# KSM_ICSP.net
KiCad netlist of a schematic drawn in EAGLE
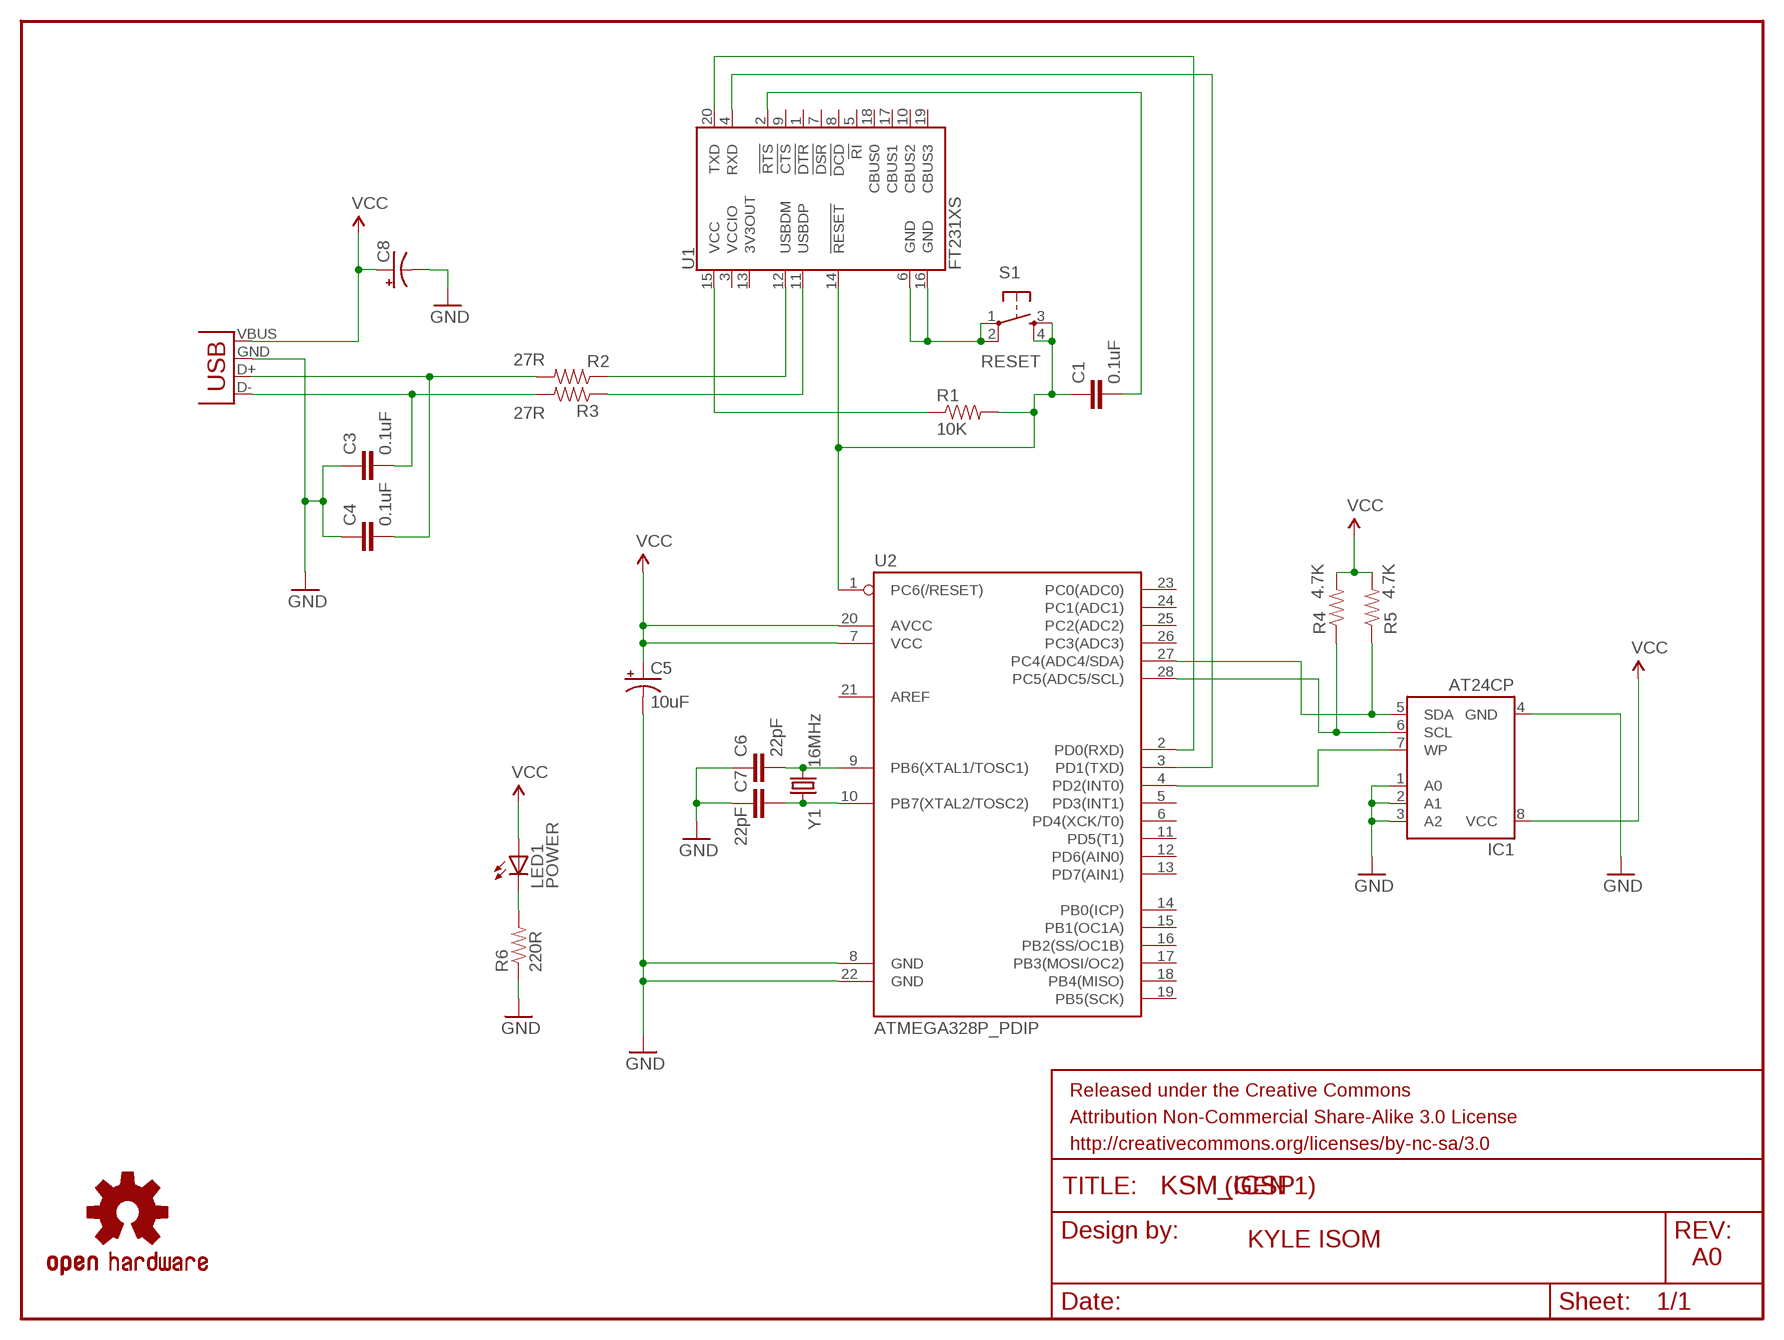
[diagram p0: schematic, sheet 1]

(export (version "E")
  (design (tool "Eeschema 10.0.6"))
  (components
    (comp (ref "C1")
      (value "0.1uF")
      (footprint "eagle-import:CAP-PTH-SMALL")
      (libsource (lib "eagle-import") (part "CAPPTH"))
    )
    (comp (ref "C3")
      (value "0.1uF")
      (footprint "eagle-import:CAP-PTH-SMALL")
      (libsource (lib "eagle-import") (part "CAPPTH"))
    )
    (comp (ref "C4")
      (value "0.1uF")
      (footprint "eagle-import:CAP-PTH-SMALL")
      (libsource (lib "eagle-import") (part "CAPPTH"))
    )
    (comp (ref "C5")
      (value "10uF")
      (footprint "eagle-import:CPOL-RADIAL-10UF-25V")
      (libsource (lib "eagle-import") (part "CAP_POLPTH2"))
    )
    (comp (ref "C6")
      (value "22pF")
      (footprint "eagle-import:CAP-PTH-SMALL")
      (libsource (lib "eagle-import") (part "CAPPTH"))
    )
    (comp (ref "C7")
      (value "22pF")
      (footprint "eagle-import:CAP-PTH-SMALL")
      (libsource (lib "eagle-import") (part "CAPPTH"))
    )
    (comp (ref "C8")
      (value "CAP_POLPTH2")
      (footprint "eagle-import:CPOL-RADIAL-10UF-25V")
      (libsource (lib "eagle-import") (part "CAP_POLPTH2"))
    )
    (comp (ref "FRAME1")
      (value "FRAME-LETTER")
      (footprint "eagle-import:CREATIVE_COMMONS")
      (libsource (lib "eagle-import") (part "FRAME-LETTER"))
    )
    (comp (ref "IC1")
      (value "AT24CP")
      (footprint "eagle-import:DIL08")
      (fields (field (name "MPN") "AT24C1024BW-SH-B"))
      (libsource (lib "eagle-import") (part "AT24CP"))
    )
    (comp (ref "JP1")
      (value "USB-A-H")
      (footprint "eagle-import:USB-A-H")
      (libsource (lib "eagle-import") (part "USB-A-H"))
    )
    (comp (ref "LED1")
      (value "POWER")
      (footprint "eagle-import:LED3MM")
      (libsource (lib "eagle-import") (part "LED3MM"))
    )
    (comp (ref "LOGO1")
      (value "OSHW-LOGOL")
      (footprint "eagle-import:OSHW-LOGO-L")
      (libsource (lib "eagle-import") (part "OSHW-LOGOL"))
    )
    (comp (ref "R1")
      (value "10K")
      (footprint "eagle-import:AXIAL-0.4")
      (libsource (lib "eagle-import") (part "RESISTORPTH-1/4W"))
    )
    (comp (ref "R2")
      (value "27R")
      (footprint "eagle-import:AXIAL-0.4")
      (libsource (lib "eagle-import") (part "RESISTORPTH-1/4W"))
    )
    (comp (ref "R3")
      (value "27R")
      (footprint "eagle-import:AXIAL-0.4")
      (libsource (lib "eagle-import") (part "RESISTORPTH-1/4W"))
    )
    (comp (ref "R4")
      (value "4.7K")
      (footprint "eagle-import:AXIAL-0.4")
      (libsource (lib "eagle-import") (part "RESISTORPTH-1/4W"))
    )
    (comp (ref "R5")
      (value "4.7K")
      (footprint "eagle-import:AXIAL-0.4")
      (libsource (lib "eagle-import") (part "RESISTORPTH-1/4W"))
    )
    (comp (ref "R6")
      (value "220R")
      (footprint "eagle-import:AXIAL-0.4")
      (libsource (lib "eagle-import") (part "RESISTORPTH-1/4W"))
    )
    (comp (ref "S1")
      (value "RESET")
      (footprint "eagle-import:TACTILE-PTH")
      (libsource (lib "eagle-import") (part "TAC_SWITCHPTH"))
    )
    (comp (ref "U1")
      (value "FT231XS")
      (footprint "eagle-import:SSOP20_L")
      (libsource (lib "eagle-import") (part "FT231XS"))
    )
    (comp (ref "U2")
      (value "ATMEGA328P_PDIP")
      (footprint "eagle-import:DIL28-3")
      (libsource (lib "eagle-import") (part "ATMEGA328P_PDIP"))
    )
    (comp (ref "Y1")
      (value "16MHz")
      (footprint "eagle-import:HC49US")
      (libsource (lib "eagle-import") (part "CRYSTALHC49US"))
    )
  )
  (nets
    (net (code "1") (name "GND") (class "Default")
      (node (ref "C3") (pin "1") (pinfunction "1_1") (pintype "passive"))
      (node (ref "C4") (pin "1") (pinfunction "1_1") (pintype "passive"))
      (node (ref "C5") (pin "2") (pinfunction "-_2") (pintype "passive"))
      (node (ref "C6") (pin "1") (pinfunction "1_1") (pintype "passive"))
      (node (ref "C7") (pin "1") (pinfunction "1_1") (pintype "passive"))
      (node (ref "C8") (pin "2") (pinfunction "-_2") (pintype "passive"))
      (node (ref "IC1") (pin "1") (pinfunction "A0_1") (pintype "input"))
      (node (ref "IC1") (pin "2") (pinfunction "A1_2") (pintype "input"))
      (node (ref "IC1") (pin "3") (pinfunction "A2_3") (pintype "input"))
      (node (ref "IC1") (pin "4") (pinfunction "GND_4") (pintype "power_in"))
      (node (ref "JP1") (pin "GND") (pinfunction "VBUS_GND") (pintype "bidirectional"))
      (node (ref "R6") (pin "P$1") (pinfunction "1_P$1") (pintype "passive"))
      (node (ref "U2") (pin "22") (pinfunction "GND_22") (pintype "bidirectional"))
      (node (ref "U2") (pin "8") (pinfunction "GND_8") (pintype "bidirectional"))
    )
    (net (code "2") (name "Net-(IC1-SCL)") (class "Default")
      (node (ref "IC1") (pin "6") (pinfunction "SCL_6") (pintype "bidirectional"))
      (node (ref "R4") (pin "P$1") (pinfunction "1_P$1") (pintype "passive"))
      (node (ref "U2") (pin "28") (pinfunction "PC5(ADC5/SCL)_28") (pintype "bidirectional"))
    )
    (net (code "3") (name "Net-(IC1-SDA)") (class "Default")
      (node (ref "IC1") (pin "5") (pinfunction "SDA_5") (pintype "bidirectional"))
      (node (ref "R5") (pin "P$1") (pinfunction "1_P$1") (pintype "passive"))
      (node (ref "U2") (pin "27") (pinfunction "PC4(ADC4/SDA)_27") (pintype "bidirectional"))
    )
    (net (code "4") (name "Net-(IC1-WP)") (class "Default")
      (node (ref "IC1") (pin "7") (pinfunction "WP_7") (pintype "input"))
      (node (ref "U2") (pin "4") (pinfunction "PD2(INT0)_4") (pintype "bidirectional"))
    )
    (net (code "5") (name "Net-(JP1-D+)") (class "Default")
      (node (ref "C3") (pin "2") (pinfunction "2_2") (pintype "passive"))
      (node (ref "JP1") (pin "D-") (pinfunction "D+_D-") (pintype "bidirectional"))
      (node (ref "R3") (pin "P$2") (pinfunction "2_P$2") (pintype "passive"))
    )
    (net (code "6") (name "Net-(JP1-D-)") (class "Default")
      (node (ref "C4") (pin "2") (pinfunction "2_2") (pintype "passive"))
      (node (ref "JP1") (pin "D+") (pinfunction "D-_D+") (pintype "bidirectional"))
      (node (ref "R2") (pin "P$2") (pinfunction "2_P$2") (pintype "passive"))
    )
    (net (code "7") (name "Net-(LED1-C)") (class "Default")
      (node (ref "LED1") (pin "K") (pinfunction "C_K") (pintype "passive"))
      (node (ref "R6") (pin "P$2") (pinfunction "2_P$2") (pintype "passive"))
    )
    (net (code "8") (name "Net-(R1-1)") (class "Default")
      (node (ref "R1") (pin "P$1") (pinfunction "1_P$1") (pintype "passive"))
      (node (ref "U1") (pin "15") (pinfunction "VCC_15") (pintype "bidirectional"))
    )
    (net (code "9") (name "Net-(R1-2)") (class "Default")
      (node (ref "C1") (pin "1") (pinfunction "1_1") (pintype "passive"))
      (node (ref "R1") (pin "P$2") (pinfunction "2_P$2") (pintype "passive"))
      (node (ref "S1") (pin "3") (pinfunction "3_3") (pintype "passive"))
      (node (ref "S1") (pin "4") (pinfunction "4_4") (pintype "passive"))
      (node (ref "U1") (pin "14") (pinfunction "~{RESET}_14") (pintype "bidirectional"))
      (node (ref "U2") (pin "1") (pinfunction "PC6(/RESET)_1") (pintype "bidirectional"))
    )
    (net (code "10") (name "Net-(R2-1)") (class "Default")
      (node (ref "R2") (pin "P$1") (pinfunction "1_P$1") (pintype "passive"))
      (node (ref "U1") (pin "12") (pinfunction "USBDM_12") (pintype "bidirectional"))
    )
    (net (code "11") (name "Net-(R3-1)") (class "Default")
      (node (ref "R3") (pin "P$1") (pinfunction "1_P$1") (pintype "passive"))
      (node (ref "U1") (pin "11") (pinfunction "USBDP_11") (pintype "bidirectional"))
    )
    (net (code "12") (name "Net-(S1-Pad1)") (class "Default")
      (node (ref "S1") (pin "1") (pinfunction "1_1") (pintype "passive"))
      (node (ref "S1") (pin "2") (pinfunction "2_2") (pintype "passive"))
      (node (ref "U1") (pin "16") (pinfunction "GND_16") (pintype "bidirectional"))
      (node (ref "U1") (pin "6") (pinfunction "GND_6") (pintype "bidirectional"))
    )
    (net (code "13") (name "Net-(U1-RXD)") (class "Default")
      (node (ref "U1") (pin "4") (pinfunction "RXD_4") (pintype "bidirectional"))
      (node (ref "U2") (pin "3") (pinfunction "PD1(TXD)_3") (pintype "bidirectional"))
    )
    (net (code "14") (name "Net-(U1-TXD)") (class "Default")
      (node (ref "U1") (pin "20") (pinfunction "TXD_20") (pintype "bidirectional"))
      (node (ref "U2") (pin "2") (pinfunction "PD0(RXD)_2") (pintype "bidirectional"))
    )
    (net (code "15") (name "Net-(U1-~{RTS})") (class "Default")
      (node (ref "C1") (pin "2") (pinfunction "2_2") (pintype "passive"))
      (node (ref "U1") (pin "2") (pinfunction "~{RTS}_2") (pintype "bidirectional"))
    )
    (net (code "16") (name "Net-(U2-PB6(XTAL1{slash}TOSC1))") (class "Default")
      (node (ref "C6") (pin "2") (pinfunction "2_2") (pintype "passive"))
      (node (ref "U2") (pin "9") (pinfunction "PB6(XTAL1/TOSC1)_9") (pintype "bidirectional"))
      (node (ref "Y1") (pin "2") (pinfunction "2_2") (pintype "passive"))
    )
    (net (code "17") (name "Net-(U2-PB7(XTAL2{slash}TOSC2))") (class "Default")
      (node (ref "C7") (pin "2") (pinfunction "2_2") (pintype "passive"))
      (node (ref "U2") (pin "10") (pinfunction "PB7(XTAL2/TOSC2)_10") (pintype "bidirectional"))
      (node (ref "Y1") (pin "1") (pinfunction "1_1") (pintype "passive"))
    )
    (net (code "18") (name "VCC") (class "Default")
      (node (ref "C5") (pin "1") (pinfunction "+_1") (pintype "passive"))
      (node (ref "C8") (pin "1") (pinfunction "+_1") (pintype "passive"))
      (node (ref "IC1") (pin "8") (pinfunction "VCC_8") (pintype "power_in"))
      (node (ref "JP1") (pin "VBUS") (pinfunction "GND_VBUS") (pintype "bidirectional"))
      (node (ref "LED1") (pin "A") (pinfunction "A_A") (pintype "passive"))
      (node (ref "R4") (pin "P$2") (pinfunction "2_P$2") (pintype "passive"))
      (node (ref "R5") (pin "P$2") (pinfunction "2_P$2") (pintype "passive"))
      (node (ref "U2") (pin "20") (pinfunction "AVCC_20") (pintype "bidirectional"))
      (node (ref "U2") (pin "7") (pinfunction "VCC_7") (pintype "bidirectional"))
    )
    (net (code "19") (name "unconnected-(U1-3V3OUT-Pad13)") (class "Default")
      (node (ref "U1") (pin "13") (pinfunction "3V3OUT_13") (pintype "bidirectional"))
    )
    (net (code "20") (name "unconnected-(U1-CBUS0-Pad18)") (class "Default")
      (node (ref "U1") (pin "18") (pinfunction "CBUS0_18") (pintype "bidirectional"))
    )
    (net (code "21") (name "unconnected-(U1-CBUS1-Pad17)") (class "Default")
      (node (ref "U1") (pin "17") (pinfunction "CBUS1_17") (pintype "bidirectional"))
    )
    (net (code "22") (name "unconnected-(U1-CBUS2-Pad10)") (class "Default")
      (node (ref "U1") (pin "10") (pinfunction "CBUS2_10") (pintype "bidirectional"))
    )
    (net (code "23") (name "unconnected-(U1-CBUS3-Pad19)") (class "Default")
      (node (ref "U1") (pin "19") (pinfunction "CBUS3_19") (pintype "bidirectional"))
    )
    (net (code "24") (name "unconnected-(U1-VCCIO-Pad3)") (class "Default")
      (node (ref "U1") (pin "3") (pinfunction "VCCIO_3") (pintype "bidirectional"))
    )
    (net (code "25") (name "unconnected-(U1-~{CTS}-Pad9)") (class "Default")
      (node (ref "U1") (pin "9") (pinfunction "~{CTS}_9") (pintype "bidirectional"))
    )
    (net (code "26") (name "unconnected-(U1-~{DCD}-Pad8)") (class "Default")
      (node (ref "U1") (pin "8") (pinfunction "~{DCD}_8") (pintype "bidirectional"))
    )
    (net (code "27") (name "unconnected-(U1-~{DSR}-Pad7)") (class "Default")
      (node (ref "U1") (pin "7") (pinfunction "~{DSR}_7") (pintype "bidirectional"))
    )
    (net (code "28") (name "unconnected-(U1-~{DTR}-Pad1)") (class "Default")
      (node (ref "U1") (pin "1") (pinfunction "~{DTR}_1") (pintype "bidirectional"))
    )
    (net (code "29") (name "unconnected-(U1-~{RI}-Pad5)") (class "Default")
      (node (ref "U1") (pin "5") (pinfunction "~{RI}_5") (pintype "bidirectional"))
    )
    (net (code "30") (name "unconnected-(U2-AREF-Pad21)") (class "Default")
      (node (ref "U2") (pin "21") (pinfunction "AREF_21") (pintype "bidirectional"))
    )
    (net (code "31") (name "unconnected-(U2-PB0(ICP)-Pad14)") (class "Default")
      (node (ref "U2") (pin "14") (pinfunction "PB0(ICP)_14") (pintype "bidirectional"))
    )
    (net (code "32") (name "unconnected-(U2-PB1(OC1A)-Pad15)") (class "Default")
      (node (ref "U2") (pin "15") (pinfunction "PB1(OC1A)_15") (pintype "bidirectional"))
    )
    (net (code "33") (name "unconnected-(U2-PB2(SS{slash}OC1B)-Pad16)") (class "Default")
      (node (ref "U2") (pin "16") (pinfunction "PB2(SS/OC1B)_16") (pintype "bidirectional"))
    )
    (net (code "34") (name "unconnected-(U2-PB3(MOSI{slash}OC2)-Pad17)") (class "Default")
      (node (ref "U2") (pin "17") (pinfunction "PB3(MOSI/OC2)_17") (pintype "bidirectional"))
    )
    (net (code "35") (name "unconnected-(U2-PB4(MISO)-Pad18)") (class "Default")
      (node (ref "U2") (pin "18") (pinfunction "PB4(MISO)_18") (pintype "bidirectional"))
    )
    (net (code "36") (name "unconnected-(U2-PB5(SCK)-Pad19)") (class "Default")
      (node (ref "U2") (pin "19") (pinfunction "PB5(SCK)_19") (pintype "bidirectional"))
    )
    (net (code "37") (name "unconnected-(U2-PC0(ADC0)-Pad23)") (class "Default")
      (node (ref "U2") (pin "23") (pinfunction "PC0(ADC0)_23") (pintype "bidirectional"))
    )
    (net (code "38") (name "unconnected-(U2-PC1(ADC1)-Pad24)") (class "Default")
      (node (ref "U2") (pin "24") (pinfunction "PC1(ADC1)_24") (pintype "bidirectional"))
    )
    (net (code "39") (name "unconnected-(U2-PC2(ADC2)-Pad25)") (class "Default")
      (node (ref "U2") (pin "25") (pinfunction "PC2(ADC2)_25") (pintype "bidirectional"))
    )
    (net (code "40") (name "unconnected-(U2-PC3(ADC3)-Pad26)") (class "Default")
      (node (ref "U2") (pin "26") (pinfunction "PC3(ADC3)_26") (pintype "bidirectional"))
    )
    (net (code "41") (name "unconnected-(U2-PD3(INT1)-Pad5)") (class "Default")
      (node (ref "U2") (pin "5") (pinfunction "PD3(INT1)_5") (pintype "bidirectional"))
    )
    (net (code "42") (name "unconnected-(U2-PD4(XCK{slash}T0)-Pad6)") (class "Default")
      (node (ref "U2") (pin "6") (pinfunction "PD4(XCK/T0)_6") (pintype "bidirectional"))
    )
    (net (code "43") (name "unconnected-(U2-PD5(T1)-Pad11)") (class "Default")
      (node (ref "U2") (pin "11") (pinfunction "PD5(T1)_11") (pintype "bidirectional"))
    )
    (net (code "44") (name "unconnected-(U2-PD6(AIN0)-Pad12)") (class "Default")
      (node (ref "U2") (pin "12") (pinfunction "PD6(AIN0)_12") (pintype "bidirectional"))
    )
    (net (code "45") (name "unconnected-(U2-PD7(AIN1)-Pad13)") (class "Default")
      (node (ref "U2") (pin "13") (pinfunction "PD7(AIN1)_13") (pintype "bidirectional"))
    )
  )
)
